# Fri3D_2024_Peripherals.net
KiCad netlist of a schematic drawn in Altium Designer
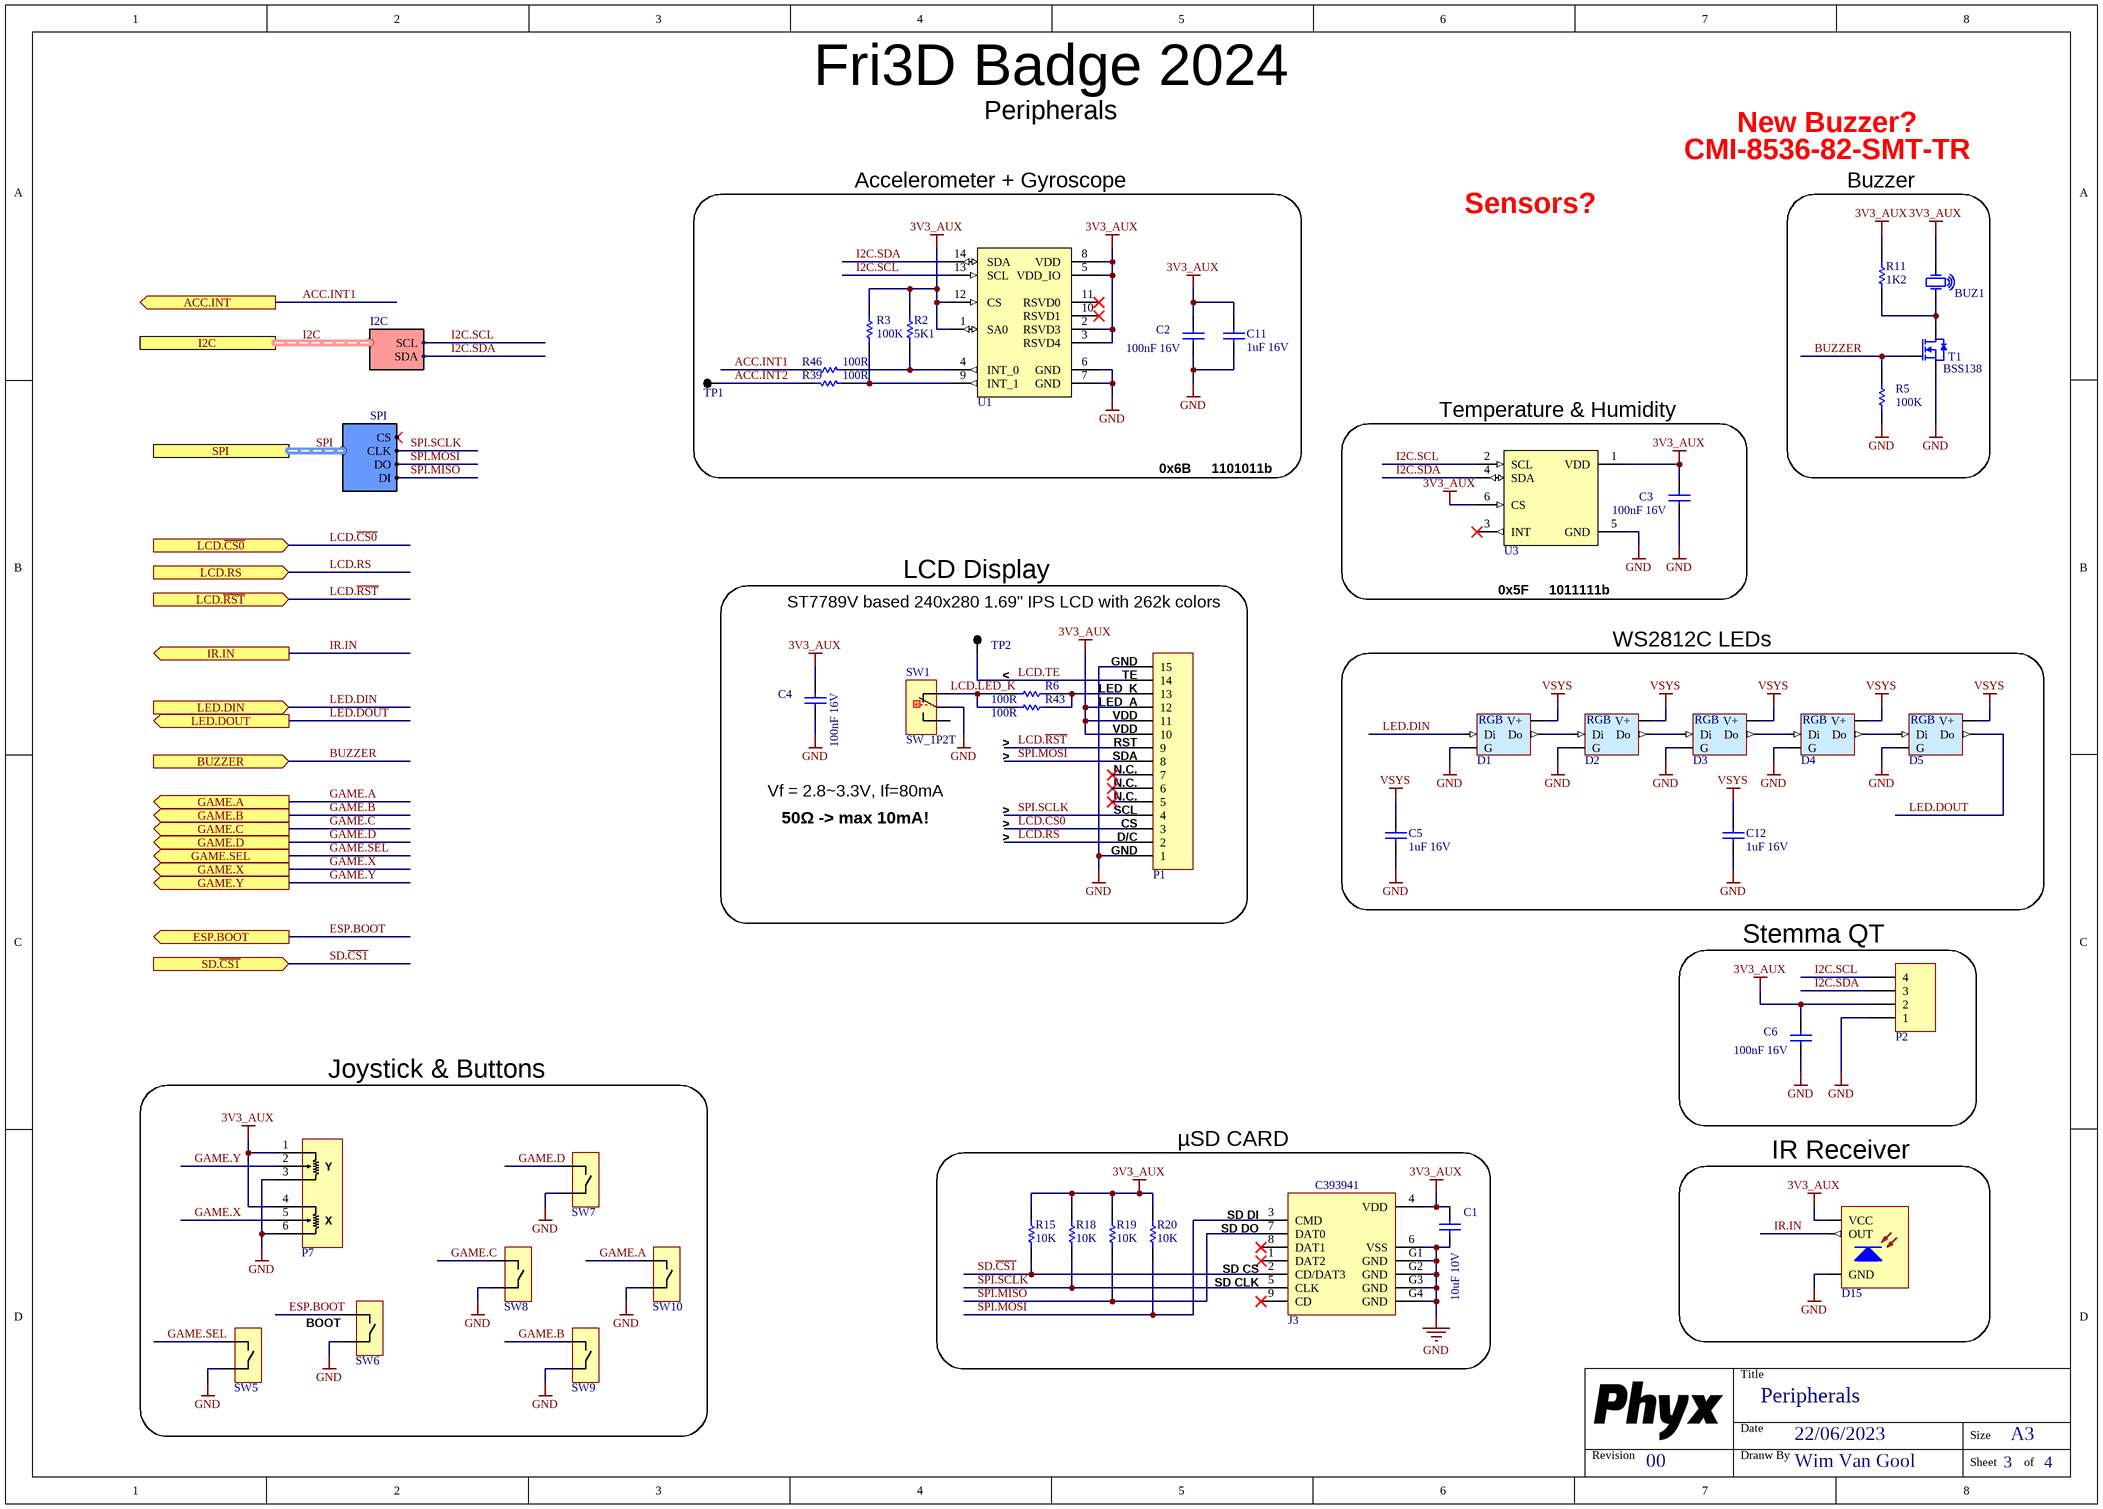
[diagram p0: Fri3D_2024_Peripherals.SchDoc]

(export (version "E")
  (design (tool "Eeschema 10.0.6"))
  (components
    (comp (ref "BUZ1")
      (value "12x12x3mm Piezo Buzzer Transducer 81dB")
      (footprint "CUI_CMT-1203-SMT")
      (description "Crystal Oscillator")
      (libsource (lib "Phyx_Components") (part "Buzzer"))
    )
    (comp (ref "C1")
      (value "10uF 10V")
      (footprint "C0805_N")
      (description "Capacitor Ceramic")
      (fields (field (name "Comment") "CAP_CERAMIC"))
      (libsource (lib "Phyx_Components") (part "CAP_CERAMIC"))
    )
    (comp (ref "C2")
      (value "100nF 16V")
      (footprint "C0603_N")
      (description "Capacitor Ceramic")
      (libsource (lib "Phyx_Components") (part "CAP_CERAMIC"))
    )
    (comp (ref "C3")
      (value "100nF 16V")
      (footprint "C0603_N")
      (description "Capacitor Ceramic")
      (libsource (lib "Phyx_Components") (part "CAP_CERAMIC"))
    )
    (comp (ref "C4")
      (value "100nF 16V")
      (footprint "C0603_N")
      (description "Capacitor Ceramic")
      (libsource (lib "Phyx_Components") (part "CAP_CERAMIC"))
    )
    (comp (ref "C5")
      (value "1uF 16V")
      (footprint "C0603_N")
      (description "Capacitor Ceramic")
      (fields (field (name "Comment") "CAP_CERAMIC"))
      (libsource (lib "Phyx_Components") (part "CAP_CERAMIC"))
    )
    (comp (ref "C6")
      (value "100nF 16V")
      (footprint "C0603_N")
      (description "Capacitor Ceramic")
      (libsource (lib "Phyx_Components") (part "CAP_CERAMIC"))
    )
    (comp (ref "C11")
      (value "1uF 16V")
      (footprint "C0603_N")
      (description "Capacitor Ceramic")
      (fields (field (name "Comment") "CAP_CERAMIC"))
      (libsource (lib "Phyx_Components") (part "CAP_CERAMIC"))
    )
    (comp (ref "C12")
      (value "1uF 16V")
      (footprint "C0603_N")
      (description "Capacitor Ceramic")
      (fields (field (name "Comment") "CAP_CERAMIC"))
      (libsource (lib "Phyx_Components") (part "CAP_CERAMIC"))
    )
    (comp (ref "D1")
      (value "WS2812 based digital RGB LED 5050 White package reduced current")
      (footprint "LED_5050_WS2812B_WHITE")
      (description "=Description")
      (libsource (lib "Phyx_Components") (part "LED_RGB_WS2812B_5050"))
    )
    (comp (ref "D2")
      (value "WS2812 based digital RGB LED 5050 White package reduced current")
      (footprint "LED_5050_WS2812B_WHITE")
      (description "=Description")
      (libsource (lib "Phyx_Components") (part "LED_RGB_WS2812B_5050"))
    )
    (comp (ref "D3")
      (value "WS2812 based digital RGB LED 5050 White package reduced current")
      (footprint "LED_5050_WS2812B_WHITE")
      (description "=Description")
      (libsource (lib "Phyx_Components") (part "LED_RGB_WS2812B_5050"))
    )
    (comp (ref "D4")
      (value "WS2812 based digital RGB LED 5050 White package reduced current")
      (footprint "LED_5050_WS2812B_WHITE")
      (description "=Description")
      (libsource (lib "Phyx_Components") (part "LED_RGB_WS2812B_5050"))
    )
    (comp (ref "D5")
      (value "WS2812 based digital RGB LED 5050 White package reduced current")
      (footprint "LED_5050_WS2812B_WHITE")
      (description "=Description")
      (libsource (lib "Phyx_Components") (part "LED_RGB_WS2812B_5050"))
    )
    (comp (ref "D15")
      (value "ZIRM-5042B-42-Z2 Infrared Receiver 38 kHz 45° 2.7-5.5V 940nm")
      (footprint "CHAU_ZIRM-5042B-42-Z2")
      (description "=Description")
      (libsource (lib "Phyx_Components") (part "PHO_IR_TSOP381x"))
    )
    (comp (ref "J3")
      (value "Micro SD PiPo Push-Push")
      (footprint "TFP09-2-12B")
      (description "=Description")
      (fields (field (name "SUPPLIER PART NUMBER 1") "C393941"))
      (libsource (lib "Phyx_Components") (part "TFP09-2-12B"))
    )
    (comp (ref "P1")
      (value "Top contact FPC 0.3mm pitch 15 contacts")
      (footprint "FPC_0.3K-HX-15PWB")
      (libsource (lib "Phyx_Components") (part "Header 15"))
    )
    (comp (ref "P2")
      (value "Header 1.0mm RA Shrouded 4")
      (footprint "WE_665104131822")
      (libsource (lib "Phyx_Components") (part "Header 4"))
    )
    (comp (ref "P7")
      (value "PSP Mini Joystick")
      (footprint "PSP_Mini_Joystick")
      (libsource (lib "Phyx_Components") (part "PSP_Mini_Joystick"))
    )
    (comp (ref "R2")
      (value "5K1")
      (footprint "R0603_N")
      (fields (field (name "Comment") "RESISTOR"))
      (libsource (lib "Phyx_Components") (part "RESISTOR"))
    )
    (comp (ref "R3")
      (value "100K")
      (footprint "R0603_N")
      (fields (field (name "Comment") "RESISTOR"))
      (libsource (lib "Phyx_Components") (part "RESISTOR"))
    )
    (comp (ref "R5")
      (value "100K")
      (footprint "R0603_N")
      (fields (field (name "Comment") "RESISTOR"))
      (libsource (lib "Phyx_Components") (part "RESISTOR"))
    )
    (comp (ref "R6")
      (value "100R")
      (footprint "R0603_N")
      (fields (field (name "Comment") "RESISTOR"))
      (libsource (lib "Phyx_Components") (part "RESISTOR"))
    )
    (comp (ref "R11")
      (value "1K2")
      (footprint "R0603_N")
      (fields (field (name "Comment") "RESISTOR"))
      (libsource (lib "Phyx_Components") (part "RESISTOR"))
    )
    (comp (ref "R15")
      (value "10K")
      (footprint "R0603_N")
      (fields (field (name "Comment") "RESISTOR"))
      (libsource (lib "Phyx_Components") (part "RESISTOR"))
    )
    (comp (ref "R18")
      (value "10K")
      (footprint "R0603_N")
      (fields (field (name "Comment") "RESISTOR"))
      (libsource (lib "Phyx_Components") (part "RESISTOR"))
    )
    (comp (ref "R19")
      (value "10K")
      (footprint "R0603_N")
      (fields (field (name "Comment") "RESISTOR"))
      (libsource (lib "Phyx_Components") (part "RESISTOR"))
    )
    (comp (ref "R20")
      (value "10K")
      (footprint "R0603_N")
      (fields (field (name "Comment") "RESISTOR"))
      (libsource (lib "Phyx_Components") (part "RESISTOR"))
    )
    (comp (ref "R39")
      (value "100R")
      (footprint "R0603_N")
      (fields (field (name "Comment") "RESISTOR"))
      (libsource (lib "Phyx_Components") (part "RESISTOR"))
    )
    (comp (ref "R43")
      (value "100R")
      (footprint "R0603_N")
      (fields (field (name "Comment") "RESISTOR"))
      (libsource (lib "Phyx_Components") (part "RESISTOR"))
    )
    (comp (ref "R46")
      (value "100R")
      (footprint "R0603_N")
      (fields (field (name "Comment") "RESISTOR"))
      (libsource (lib "Phyx_Components") (part "RESISTOR"))
    )
    (comp (ref "SW1")
      (value "SW_1P2T")
      (footprint "WE_450404015514")
      (libsource (lib "Phyx_Components") (part "SW_1P2T"))
    )
    (comp (ref "SW5")
      (value "SKPMAME010 6x6 TACTG Switch")
      (footprint "ALPS_SKPMAME010")
      (libsource (lib "Phyx_Components") (part "SW_TACT"))
    )
    (comp (ref "SW6")
      (value "SKPMAME010 6x6 TACTG Switch")
      (footprint "ALPS_SKPMAME010")
      (libsource (lib "Phyx_Components") (part "SW_TACT"))
    )
    (comp (ref "SW7")
      (value "SKPMAME010 6x6 TACTG Switch")
      (footprint "ALPS_SKPMAME010")
      (libsource (lib "Phyx_Components") (part "SW_TACT"))
    )
    (comp (ref "SW8")
      (value "SKPMAME010 6x6 TACTG Switch")
      (footprint "ALPS_SKPMAME010")
      (libsource (lib "Phyx_Components") (part "SW_TACT"))
    )
    (comp (ref "SW9")
      (value "SKPMAME010 6x6 TACTG Switch")
      (footprint "ALPS_SKPMAME010")
      (libsource (lib "Phyx_Components") (part "SW_TACT"))
    )
    (comp (ref "SW10")
      (value "SKPMAME010 6x6 TACTG Switch")
      (footprint "ALPS_SKPMAME010")
      (libsource (lib "Phyx_Components") (part "SW_TACT"))
    )
    (comp (ref "T1")
      (value "BSS138")
      (footprint "SOT23-3")
      (fields (field (name "Comment") "0.2A N-Ch MOSFET Vgs 3.2"))
      (libsource (lib "Phyx_Components") (part "N_MOSFET_GSD"))
    )
    (comp (ref "TP1")
      (value "TEST_PAD")
      (footprint "TP_1.2mm")
      (libsource (lib "Phyx_Components") (part "TEST_PAD"))
    )
    (comp (ref "TP2")
      (value "TEST_PAD")
      (footprint "TP_1.2mm")
      (libsource (lib "Phyx_Components") (part "TEST_PAD"))
    )
    (comp (ref "U1")
      (value "Acceleration ±2, ±4, ±8, ±16g Gyro ±125, ±250, ±500, ±1000, ±2000dps")
      (footprint "WE_2536030320001")
      (description "=Description")
      (libsource (lib "Phyx_Components") (part "WE_2536030320001"))
    )
    (comp (ref "U3")
      (value "WSEN-HIDS 2525020210001 temperature and humidity sensor Digital I2C")
      (footprint "WE_2525020210001")
      (description "=Description")
      (libsource (lib "Phyx_Components") (part "WE_2525020210001"))
    )
  )
  (nets
    (net (code "3") (name "/ACC.INT1") (class "Default")
      (node (ref "R46") (pin "2") (pinfunction "2_2") (pintype "passive"))
    )
    (net (code "4") (name "/ACC.INT2") (class "Default")
      (node (ref "R39") (pin "2") (pinfunction "2_2") (pintype "passive"))
      (node (ref "TP1") (pin "1") (pinfunction "1_1") (pintype "passive"))
    )
    (net (code "5") (name "/BUZZER") (class "Default")
      (node (ref "R5") (pin "1") (pinfunction "1_1") (pintype "passive"))
      (node (ref "T1") (pin "1") (pinfunction "G_1") (pintype "passive"))
    )
    (net (code "6") (name "/ESP.BOOT") (class "Default")
      (node (ref "SW6") (pin "1") (pinfunction "1_1") (pintype "passive"))
    )
    (net (code "7") (name "/GAME.A") (class "Default")
      (node (ref "SW10") (pin "1") (pinfunction "1_1") (pintype "passive"))
    )
    (net (code "8") (name "/GAME.B") (class "Default")
      (node (ref "SW9") (pin "1") (pinfunction "1_1") (pintype "passive"))
    )
    (net (code "9") (name "/GAME.C") (class "Default")
      (node (ref "SW8") (pin "1") (pinfunction "1_1") (pintype "passive"))
    )
    (net (code "10") (name "/GAME.D") (class "Default")
      (node (ref "SW7") (pin "1") (pinfunction "1_1") (pintype "passive"))
    )
    (net (code "11") (name "/GAME.SEL") (class "Default")
      (node (ref "SW5") (pin "1") (pinfunction "1_1") (pintype "passive"))
    )
    (net (code "12") (name "/GAME.X") (class "Default")
      (node (ref "P7") (pin "5") (pinfunction "5_5") (pintype "passive"))
    )
    (net (code "13") (name "/GAME.Y") (class "Default")
      (node (ref "P7") (pin "2") (pinfunction "2_2") (pintype "passive"))
    )
    (net (code "14") (name "/I2C.SCL") (class "Default")
      (node (ref "P2") (pin "4") (pinfunction "4_4") (pintype "passive"))
      (node (ref "U1") (pin "13") (pinfunction "SCL_13") (pintype "input"))
      (node (ref "U3") (pin "2") (pinfunction "SCL_2") (pintype "input"))
    )
    (net (code "15") (name "/I2C.SDA") (class "Default")
      (node (ref "P2") (pin "3") (pinfunction "3_3") (pintype "passive"))
      (node (ref "U1") (pin "14") (pinfunction "SDA_14") (pintype "bidirectional"))
      (node (ref "U3") (pin "4") (pinfunction "SDA_4") (pintype "bidirectional"))
    )
    (net (code "17") (name "/IR.IN") (class "Default")
      (node (ref "D15") (pin "1") (pinfunction "OUT_1") (pintype "output"))
    )
    (net (code "18") (name "/LCD.LED_K") (class "Default")
      (node (ref "R43") (pin "2") (pinfunction "2_2") (pintype "passive"))
      (node (ref "R6") (pin "2") (pinfunction "2_2") (pintype "passive"))
      (node (ref "SW1") (pin "1") (pinfunction "1_1") (pintype "passive"))
    )
    (net (code "19") (name "/LCD.RS") (class "Default")
      (node (ref "P1") (pin "2") (pinfunction "2_2") (pintype "passive"))
    )
    (net (code "20") (name "/LCD.TE") (class "Default")
      (node (ref "P1") (pin "14") (pinfunction "14_14") (pintype "passive"))
      (node (ref "TP2") (pin "1") (pinfunction "1_1") (pintype "passive"))
    )
    (net (code "21") (name "/LCD.~{CS0}") (class "Default")
      (node (ref "P1") (pin "3") (pinfunction "3_3") (pintype "passive"))
    )
    (net (code "22") (name "/LCD.~{RST}") (class "Default")
      (node (ref "P1") (pin "9") (pinfunction "9_9") (pintype "passive"))
    )
    (net (code "23") (name "/LED.DIN") (class "Default")
      (node (ref "D1") (pin "4") (pinfunction "Di_4") (pintype "input"))
    )
    (net (code "24") (name "/LED.DOUT") (class "Default")
      (node (ref "D5") (pin "2") (pinfunction "Do_2") (pintype "output"))
    )
    (net (code "25") (name "/SD.~{CS1}") (class "Default")
      (node (ref "J3") (pin "2") (pinfunction "CD/DAT3_2") (pintype "passive"))
      (node (ref "R15") (pin "2") (pinfunction "2_2") (pintype "passive"))
    )
    (net (code "26") (name "/SPI.MISO") (class "Default")
      (node (ref "J3") (pin "7") (pinfunction "DAT0_7") (pintype "passive"))
      (node (ref "R19") (pin "2") (pinfunction "2_2") (pintype "passive"))
    )
    (net (code "27") (name "/SPI.MOSI") (class "Default")
      (node (ref "J3") (pin "3") (pinfunction "CMD_3") (pintype "passive"))
      (node (ref "P1") (pin "8") (pinfunction "8_8") (pintype "passive"))
      (node (ref "R20") (pin "2") (pinfunction "2_2") (pintype "passive"))
    )
    (net (code "28") (name "/SPI.SCLK") (class "Default")
      (node (ref "J3") (pin "5") (pinfunction "CLK_5") (pintype "passive"))
      (node (ref "P1") (pin "4") (pinfunction "4_4") (pintype "passive"))
      (node (ref "R18") (pin "2") (pinfunction "2_2") (pintype "passive"))
    )
    (net (code "30") (name "3V3_AUX") (class "Default")
      (node (ref "BUZ1") (pin "2") (pinfunction "OSC2_2") (pintype "passive"))
      (node (ref "C1") (pin "1") (pinfunction "1_1") (pintype "passive"))
      (node (ref "C11") (pin "1") (pinfunction "1_1") (pintype "passive"))
      (node (ref "C2") (pin "1") (pinfunction "1_1") (pintype "passive"))
      (node (ref "C3") (pin "1") (pinfunction "1_1") (pintype "passive"))
      (node (ref "C4") (pin "1") (pinfunction "1_1") (pintype "passive"))
      (node (ref "C6") (pin "1") (pinfunction "1_1") (pintype "passive"))
      (node (ref "D15") (pin "3") (pinfunction "VCC_3") (pintype "power_in"))
      (node (ref "J3") (pin "4") (pinfunction "VDD_4") (pintype "power_in"))
      (node (ref "P1") (pin "10") (pinfunction "10_10") (pintype "passive"))
      (node (ref "P1") (pin "11") (pinfunction "11_11") (pintype "passive"))
      (node (ref "P1") (pin "12") (pinfunction "12_12") (pintype "passive"))
      (node (ref "P2") (pin "2") (pinfunction "2_2") (pintype "passive"))
      (node (ref "P7") (pin "1") (pinfunction "1_1") (pintype "passive"))
      (node (ref "P7") (pin "4") (pinfunction "4_4") (pintype "passive"))
      (node (ref "R11") (pin "2") (pinfunction "2_2") (pintype "passive"))
      (node (ref "R15") (pin "1") (pinfunction "1_1") (pintype "passive"))
      (node (ref "R18") (pin "1") (pinfunction "1_1") (pintype "passive"))
      (node (ref "R19") (pin "1") (pinfunction "1_1") (pintype "passive"))
      (node (ref "R2") (pin "1") (pinfunction "1_1") (pintype "passive"))
      (node (ref "R20") (pin "1") (pinfunction "1_1") (pintype "passive"))
      (node (ref "R3") (pin "1") (pinfunction "1_1") (pintype "passive"))
      (node (ref "U1") (pin "1") (pinfunction "SA0_1") (pintype "bidirectional"))
      (node (ref "U1") (pin "12") (pinfunction "CS_12") (pintype "input"))
      (node (ref "U1") (pin "2") (pinfunction "RSVD3_2") (pintype "passive"))
      (node (ref "U1") (pin "3") (pinfunction "RSVD4_3") (pintype "passive"))
      (node (ref "U1") (pin "5") (pinfunction "VDD_IO_5") (pintype "power_in"))
      (node (ref "U1") (pin "8") (pinfunction "VDD_8") (pintype "power_in"))
      (node (ref "U3") (pin "1") (pinfunction "VDD_1") (pintype "power_in"))
      (node (ref "U3") (pin "6") (pinfunction "CS_6") (pintype "input"))
    )
    (net (code "31") (name "GND") (class "Default")
      (node (ref "C1") (pin "2") (pinfunction "2_2") (pintype "passive"))
      (node (ref "C11") (pin "2") (pinfunction "2_2") (pintype "passive"))
      (node (ref "C12") (pin "2") (pinfunction "2_2") (pintype "passive"))
      (node (ref "C2") (pin "2") (pinfunction "2_2") (pintype "passive"))
      (node (ref "C3") (pin "2") (pinfunction "2_2") (pintype "passive"))
      (node (ref "C4") (pin "2") (pinfunction "2_2") (pintype "passive"))
      (node (ref "C5") (pin "2") (pinfunction "2_2") (pintype "passive"))
      (node (ref "C6") (pin "2") (pinfunction "2_2") (pintype "passive"))
      (node (ref "D1") (pin "3") (pinfunction "G_3") (pintype "power_in"))
      (node (ref "D15") (pin "2") (pinfunction "GND_2") (pintype "power_in"))
      (node (ref "D2") (pin "3") (pinfunction "G_3") (pintype "power_in"))
      (node (ref "D3") (pin "3") (pinfunction "G_3") (pintype "power_in"))
      (node (ref "D4") (pin "3") (pinfunction "G_3") (pintype "power_in"))
      (node (ref "D5") (pin "3") (pinfunction "G_3") (pintype "power_in"))
      (node (ref "J3") (pin "6") (pinfunction "VSS_6") (pintype "power_in"))
      (node (ref "J3") (pin "G1") (pinfunction "GND_G1") (pintype "power_in"))
      (node (ref "J3") (pin "G2") (pinfunction "GND_G2") (pintype "power_in"))
      (node (ref "J3") (pin "G3") (pinfunction "GND_G3") (pintype "power_in"))
      (node (ref "J3") (pin "G4") (pinfunction "GND_G4") (pintype "power_in"))
      (node (ref "P1") (pin "1") (pinfunction "1_1") (pintype "passive"))
      (node (ref "P1") (pin "15") (pinfunction "15_15") (pintype "passive"))
      (node (ref "P2") (pin "1") (pinfunction "1_1") (pintype "passive"))
      (node (ref "P7") (pin "3") (pinfunction "3_3") (pintype "passive"))
      (node (ref "P7") (pin "6") (pinfunction "6_6") (pintype "passive"))
      (node (ref "R5") (pin "2") (pinfunction "2_2") (pintype "passive"))
      (node (ref "SW1") (pin "2") (pinfunction "2_2") (pintype "passive"))
      (node (ref "SW10") (pin "2") (pinfunction "2_2") (pintype "passive"))
      (node (ref "SW5") (pin "2") (pinfunction "2_2") (pintype "passive"))
      (node (ref "SW6") (pin "2") (pinfunction "2_2") (pintype "passive"))
      (node (ref "SW7") (pin "2") (pinfunction "2_2") (pintype "passive"))
      (node (ref "SW8") (pin "2") (pinfunction "2_2") (pintype "passive"))
      (node (ref "SW9") (pin "2") (pinfunction "2_2") (pintype "passive"))
      (node (ref "T1") (pin "2") (pinfunction "S_2") (pintype "passive"))
      (node (ref "U1") (pin "6") (pinfunction "GND_6") (pintype "power_in"))
      (node (ref "U1") (pin "7") (pinfunction "GND_7") (pintype "power_in"))
      (node (ref "U3") (pin "5") (pinfunction "GND_5") (pintype "power_in"))
    )
    (net (code "32") (name "Net-(BUZ1-OSC1)") (class "Default")
      (node (ref "BUZ1") (pin "1") (pinfunction "OSC1_1") (pintype "passive"))
      (node (ref "R11") (pin "1") (pinfunction "1_1") (pintype "passive"))
      (node (ref "T1") (pin "3") (pinfunction "D_3") (pintype "passive"))
    )
    (net (code "33") (name "Net-(D1-Do)") (class "Default")
      (node (ref "D1") (pin "2") (pinfunction "Do_2") (pintype "output"))
      (node (ref "D2") (pin "4") (pinfunction "Di_4") (pintype "input"))
    )
    (net (code "34") (name "Net-(D2-Do)") (class "Default")
      (node (ref "D2") (pin "2") (pinfunction "Do_2") (pintype "output"))
      (node (ref "D3") (pin "4") (pinfunction "Di_4") (pintype "input"))
    )
    (net (code "35") (name "Net-(D3-Do)") (class "Default")
      (node (ref "D3") (pin "2") (pinfunction "Do_2") (pintype "output"))
      (node (ref "D4") (pin "4") (pinfunction "Di_4") (pintype "input"))
    )
    (net (code "36") (name "Net-(D4-Do)") (class "Default")
      (node (ref "D4") (pin "2") (pinfunction "Do_2") (pintype "output"))
      (node (ref "D5") (pin "4") (pinfunction "Di_4") (pintype "input"))
    )
    (net (code "37") (name "Net-(P1-Pad13)") (class "Default")
      (node (ref "P1") (pin "13") (pinfunction "13_13") (pintype "passive"))
      (node (ref "R43") (pin "1") (pinfunction "1_1") (pintype "passive"))
      (node (ref "R6") (pin "1") (pinfunction "1_1") (pintype "passive"))
    )
    (net (code "38") (name "Net-(U1-INT_0)") (class "Default")
      (node (ref "R2") (pin "2") (pinfunction "2_2") (pintype "passive"))
      (node (ref "R46") (pin "1") (pinfunction "1_1") (pintype "passive"))
      (node (ref "U1") (pin "4") (pinfunction "INT_0_4") (pintype "output"))
    )
    (net (code "39") (name "Net-(U1-INT_1)") (class "Default")
      (node (ref "R3") (pin "2") (pinfunction "2_2") (pintype "passive"))
      (node (ref "R39") (pin "1") (pinfunction "1_1") (pintype "passive"))
      (node (ref "U1") (pin "9") (pinfunction "INT_1_9") (pintype "output"))
    )
    (net (code "40") (name "VSYS") (class "Default")
      (node (ref "C12") (pin "1") (pinfunction "1_1") (pintype "passive"))
      (node (ref "C5") (pin "1") (pinfunction "1_1") (pintype "passive"))
      (node (ref "D1") (pin "1") (pinfunction "V+_1") (pintype "power_in"))
      (node (ref "D2") (pin "1") (pinfunction "V+_1") (pintype "power_in"))
      (node (ref "D3") (pin "1") (pinfunction "V+_1") (pintype "power_in"))
      (node (ref "D4") (pin "1") (pinfunction "V+_1") (pintype "power_in"))
      (node (ref "D5") (pin "1") (pinfunction "V+_1") (pintype "power_in"))
    )
    (net (code "41") (name "unconnected-(J3-CD-Pad9)") (class "Default")
      (node (ref "J3") (pin "9") (pinfunction "CD_9") (pintype "passive+no_connect"))
    )
    (net (code "42") (name "unconnected-(J3-DAT1-Pad8)") (class "Default")
      (node (ref "J3") (pin "8") (pinfunction "DAT1_8") (pintype "passive+no_connect"))
    )
    (net (code "43") (name "unconnected-(J3-DAT2-Pad1)") (class "Default")
      (node (ref "J3") (pin "1") (pinfunction "DAT2_1") (pintype "passive+no_connect"))
    )
    (net (code "44") (name "unconnected-(P1-Pad5)") (class "Default")
      (node (ref "P1") (pin "5") (pinfunction "5_5") (pintype "passive+no_connect"))
    )
    (net (code "45") (name "unconnected-(P1-Pad6)") (class "Default")
      (node (ref "P1") (pin "6") (pinfunction "6_6") (pintype "passive+no_connect"))
    )
    (net (code "46") (name "unconnected-(P1-Pad7)") (class "Default")
      (node (ref "P1") (pin "7") (pinfunction "7_7") (pintype "passive+no_connect"))
    )
    (net (code "47") (name "unconnected-(SW1-Pad3)") (class "Default")
      (node (ref "SW1") (pin "3") (pinfunction "3_3") (pintype "passive"))
    )
    (net (code "48") (name "unconnected-(U1-RSVD0-Pad11)") (class "Default")
      (node (ref "U1") (pin "11") (pinfunction "RSVD0_11") (pintype "passive+no_connect"))
    )
    (net (code "49") (name "unconnected-(U1-RSVD1-Pad10)") (class "Default")
      (node (ref "U1") (pin "10") (pinfunction "RSVD1_10") (pintype "passive+no_connect"))
    )
    (net (code "50") (name "unconnected-(U3-INT-Pad3)") (class "Default")
      (node (ref "U3") (pin "3") (pinfunction "INT_3") (pintype "output+no_connect"))
    )
  )
)
